# Bats_n_Gons.net
KiCad netlist of a schematic drawn in EAGLE
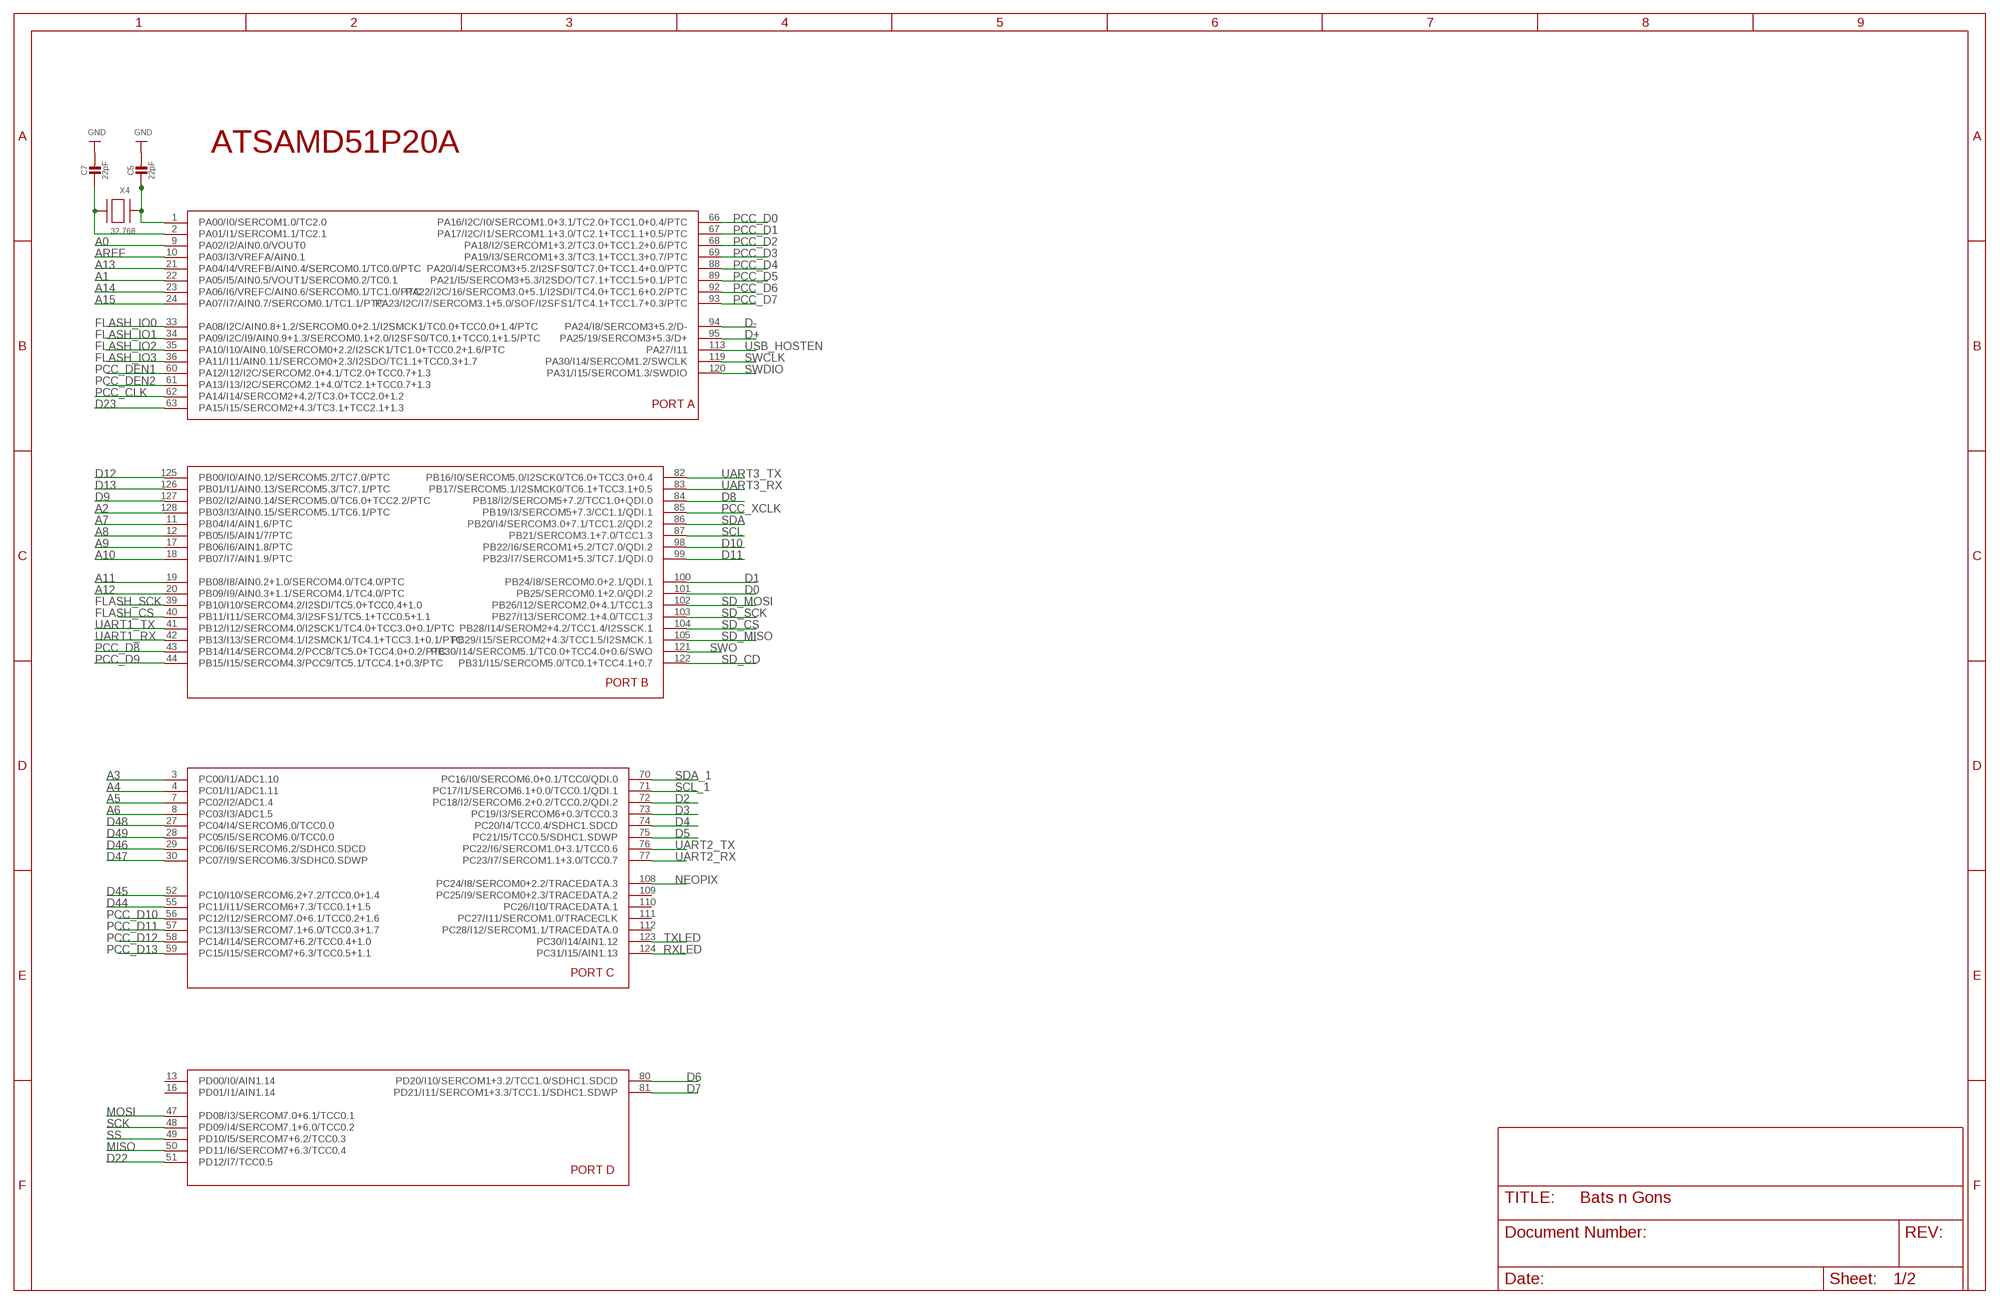
[diagram p0: schematic, sheet 1]
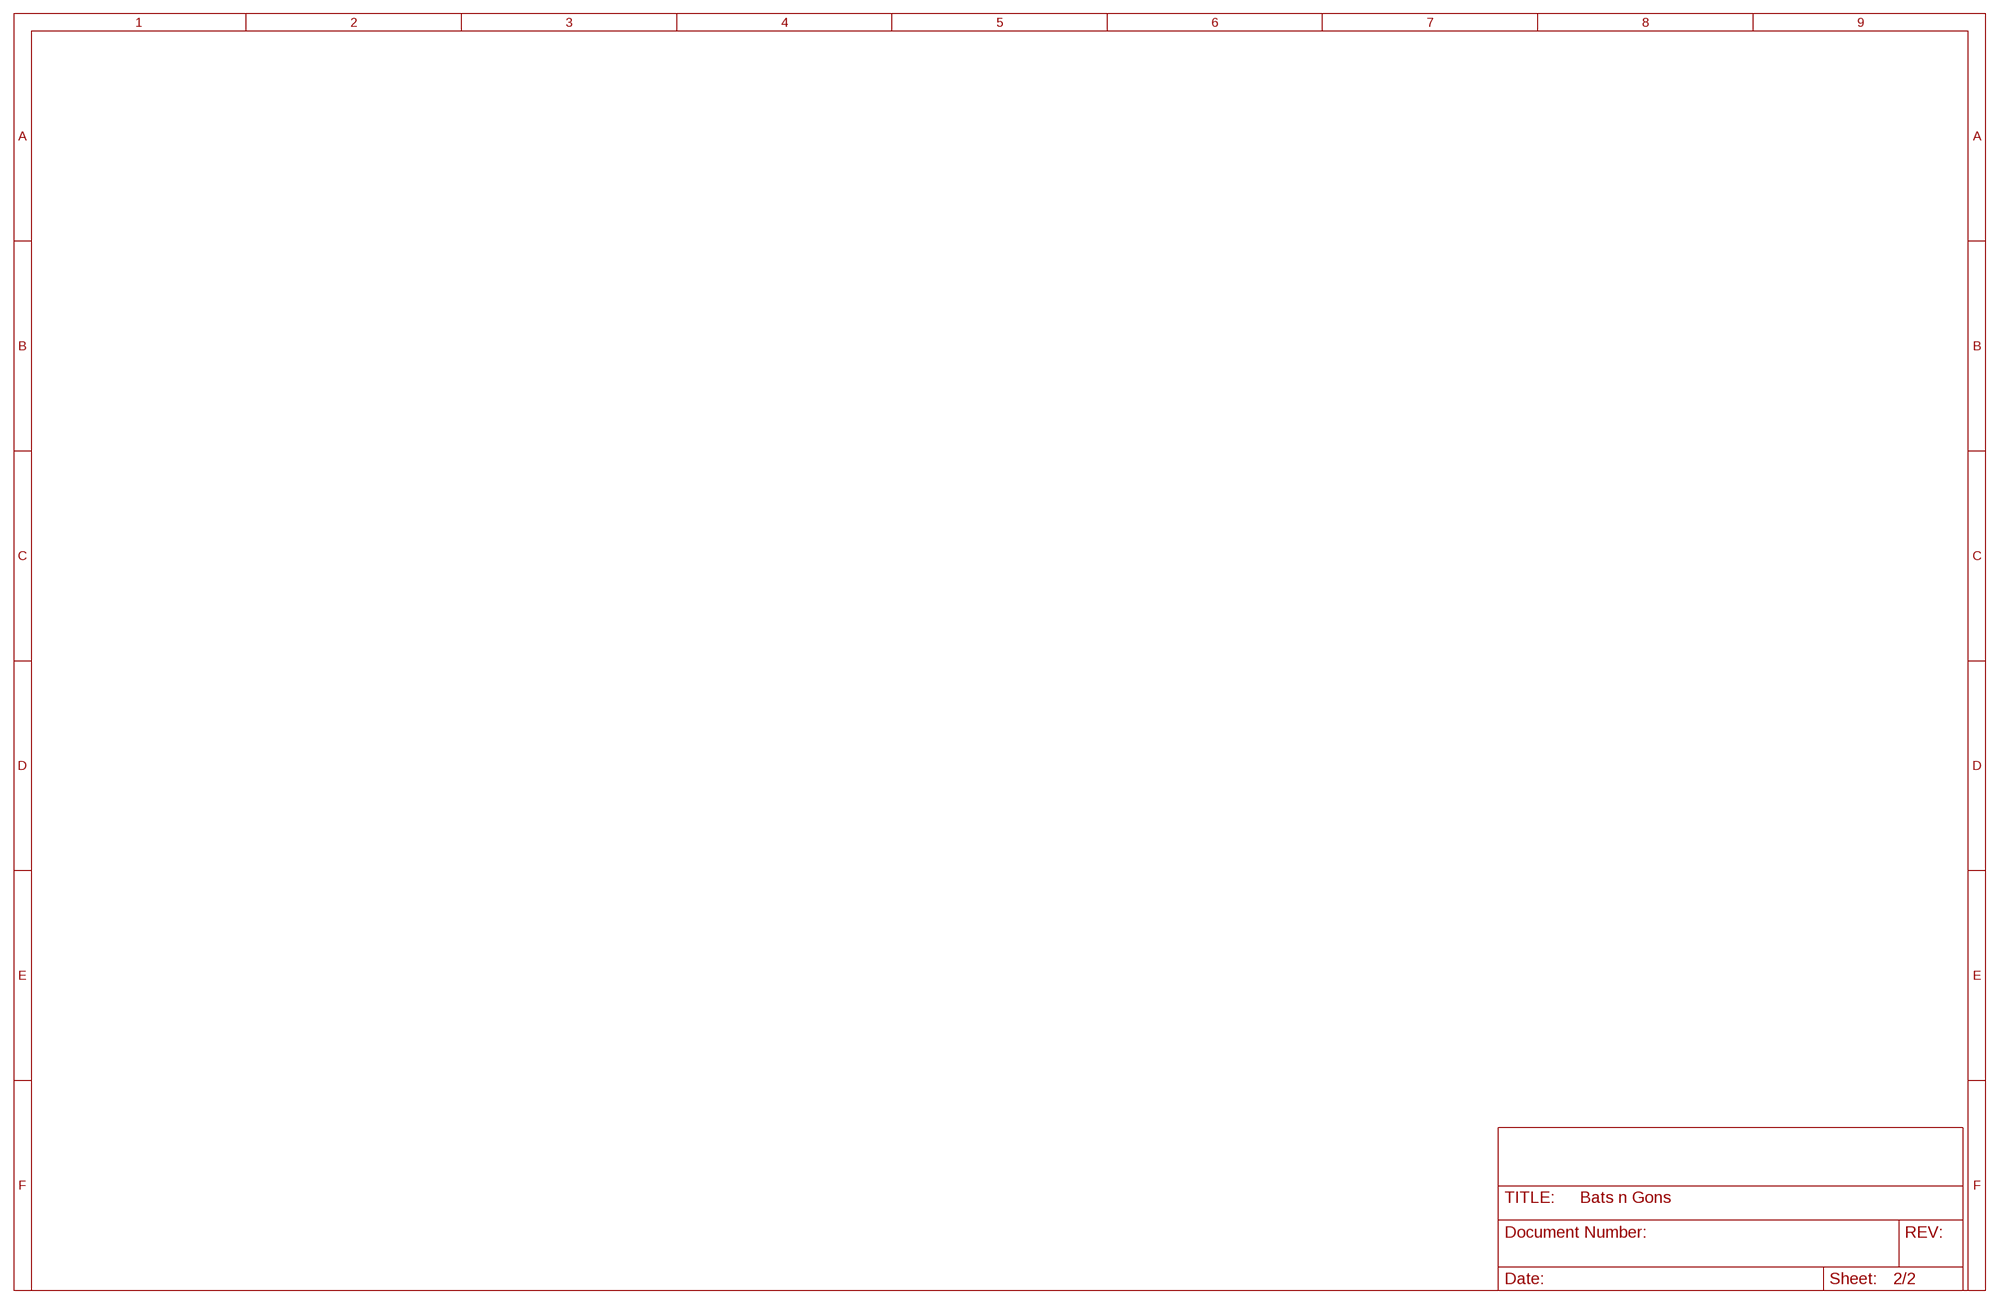
[diagram p1: schematic, sheet 2]

(export (version "E")
  (design (tool "Eeschema 10.0.6"))
  (components
    (comp (ref "C5")
      (value "22pF")
      (footprint "eagle-import:0603-NO")
      (libsource (lib "eagle-import") (part "CAP_CERAMIC0603_NO"))
    )
    (comp (ref "C7")
      (value "22pF")
      (footprint "eagle-import:0603-NO")
      (libsource (lib "eagle-import") (part "CAP_CERAMIC0603_NO"))
    )
    (comp (ref "U$1")
      (value "SAMD51PXXA")
      (footprint "eagle-import:SQFP-S-14X14-128")
      (libsource (lib "eagle-import") (part "SAMD51PXXA"))
    )
    (comp (ref "X4")
      (value "32.768")
      (footprint "eagle-import:XTAL3215")
      (libsource (lib "eagle-import") (part "XTAL-3.2X1.5"))
    )
  )
  (nets
    (net (code "1") (name "A0") (class "Default")
      (node (ref "U$1") (pin "9") (pinfunction "PA02/I2/AIN0.0/VOUT0_9") (pintype "bidirectional"))
    )
    (net (code "2") (name "A1") (class "Default")
      (node (ref "U$1") (pin "22") (pinfunction "PA05/I5/AIN0.5/VOUT1/SERCOM0.2/TC0.1_22") (pintype "bidirectional"))
    )
    (net (code "3") (name "A2") (class "Default")
      (node (ref "U$1") (pin "128") (pinfunction "PB03/I3/AIN0.15/SERCOM5.1/TC6.1/PTC_128") (pintype "bidirectional"))
    )
    (net (code "4") (name "A3") (class "Default")
      (node (ref "U$1") (pin "3") (pinfunction "PC00/I1/ADC1.10_3") (pintype "bidirectional"))
    )
    (net (code "5") (name "A4") (class "Default")
      (node (ref "U$1") (pin "4") (pinfunction "PC01/I1/ADC1.11_4") (pintype "bidirectional"))
    )
    (net (code "6") (name "A5") (class "Default")
      (node (ref "U$1") (pin "7") (pinfunction "PC02/I2/ADC1.4_7") (pintype "bidirectional"))
    )
    (net (code "7") (name "A6") (class "Default")
      (node (ref "U$1") (pin "8") (pinfunction "PC03/I3/ADC1.5_8") (pintype "bidirectional"))
    )
    (net (code "8") (name "A7") (class "Default")
      (node (ref "U$1") (pin "11") (pinfunction "PB04/I4/AIN1.6/PTC_11") (pintype "bidirectional"))
    )
    (net (code "9") (name "A8") (class "Default")
      (node (ref "U$1") (pin "12") (pinfunction "PB05/I5/AIN1/7/PTC_12") (pintype "bidirectional"))
    )
    (net (code "10") (name "A9") (class "Default")
      (node (ref "U$1") (pin "17") (pinfunction "PB06/I6/AIN1.8/PTC_17") (pintype "bidirectional"))
    )
    (net (code "11") (name "A10") (class "Default")
      (node (ref "U$1") (pin "18") (pinfunction "PB07/I7/AIN1.9/PTC_18") (pintype "bidirectional"))
    )
    (net (code "12") (name "A11") (class "Default")
      (node (ref "U$1") (pin "19") (pinfunction "PB08/I8/AIN0.2+1.0/SERCOM4.0/TC4.0/PTC_19") (pintype "bidirectional"))
    )
    (net (code "13") (name "A12") (class "Default")
      (node (ref "U$1") (pin "20") (pinfunction "PB09/I9/AIN0.3+1.1/SERCOM4.1/TC4.0/PTC_20") (pintype "bidirectional"))
    )
    (net (code "14") (name "A13") (class "Default")
      (node (ref "U$1") (pin "21") (pinfunction "PA04/I4/VREFB/AIN0.4/SERCOM0.1/TC0.0/PTC_21") (pintype "bidirectional"))
    )
    (net (code "15") (name "A14") (class "Default")
      (node (ref "U$1") (pin "23") (pinfunction "PA06/I6/VREFC/AIN0.6/SERCOM0.1/TC1.0/PTC_23") (pintype "bidirectional"))
    )
    (net (code "16") (name "A15") (class "Default")
      (node (ref "U$1") (pin "24") (pinfunction "PA07/I7/AIN0.7/SERCOM0.1/TC1.1/PTC_24") (pintype "bidirectional"))
    )
    (net (code "17") (name "AREF") (class "Default")
      (node (ref "U$1") (pin "10") (pinfunction "PA03/I3/VREFA/AIN0.1_10") (pintype "bidirectional"))
    )
    (net (code "18") (name "D+") (class "Default")
      (node (ref "U$1") (pin "95") (pinfunction "PA25/19/SERCOM3+5.3/D+_95") (pintype "bidirectional"))
    )
    (net (code "19") (name "D-") (class "Default")
      (node (ref "U$1") (pin "94") (pinfunction "PA24/I8/SERCOM3+5.2/D-_94") (pintype "bidirectional"))
    )
    (net (code "20") (name "D0") (class "Default")
      (node (ref "U$1") (pin "101") (pinfunction "PB25/SERCOM0.1+2.0/QDI.2_101") (pintype "bidirectional"))
    )
    (net (code "21") (name "D1") (class "Default")
      (node (ref "U$1") (pin "100") (pinfunction "PB24/I8/SERCOM0.0+2.1/QDI.1_100") (pintype "bidirectional"))
    )
    (net (code "22") (name "D2") (class "Default")
      (node (ref "U$1") (pin "72") (pinfunction "PC18/I2/SERCOM6.2+0.2/TCC0.2/QDI.2_72") (pintype "bidirectional"))
    )
    (net (code "23") (name "D3") (class "Default")
      (node (ref "U$1") (pin "73") (pinfunction "PC19/I3/SERCOM6+0.3/TCC0.3_73") (pintype "bidirectional"))
    )
    (net (code "24") (name "D4") (class "Default")
      (node (ref "U$1") (pin "74") (pinfunction "PC20/I4/TCC0.4/SDHC1.SDCD_74") (pintype "bidirectional"))
    )
    (net (code "25") (name "D5") (class "Default")
      (node (ref "U$1") (pin "75") (pinfunction "PC21/I5/TCC0.5/SDHC1.SDWP_75") (pintype "bidirectional"))
    )
    (net (code "26") (name "D6") (class "Default")
      (node (ref "U$1") (pin "80") (pinfunction "PD20/I10/SERCOM1+3.2/TCC1.0/SDHC1.SDCD_80") (pintype "bidirectional"))
    )
    (net (code "27") (name "D7") (class "Default")
      (node (ref "U$1") (pin "81") (pinfunction "PD21/I11/SERCOM1+3.3/TCC1.1/SDHC1.SDWP_81") (pintype "bidirectional"))
    )
    (net (code "28") (name "D8") (class "Default")
      (node (ref "U$1") (pin "84") (pinfunction "PB18/I2/SERCOM5+7.2/TCC1.0+QDI.0_84") (pintype "bidirectional"))
    )
    (net (code "29") (name "D9") (class "Default")
      (node (ref "U$1") (pin "127") (pinfunction "PB02/I2/AIN0.14/SERCOM5.0/TC6.0+TCC2.2/PTC_127") (pintype "bidirectional"))
    )
    (net (code "30") (name "D10") (class "Default")
      (node (ref "U$1") (pin "98") (pinfunction "PB22/I6/SERCOM1+5.2/TC7.0/QDI.2_98") (pintype "bidirectional"))
    )
    (net (code "31") (name "D11") (class "Default")
      (node (ref "U$1") (pin "99") (pinfunction "PB23/I7/SERCOM1+5.3/TC7.1/QDI.0_99") (pintype "bidirectional"))
    )
    (net (code "32") (name "D12") (class "Default")
      (node (ref "U$1") (pin "125") (pinfunction "PB00/I0/AIN0.12/SERCOM5.2/TC7.0/PTC_125") (pintype "bidirectional"))
    )
    (net (code "33") (name "D13") (class "Default")
      (node (ref "U$1") (pin "126") (pinfunction "PB01/I1/AIN0.13/SERCOM5.3/TC7.1/PTC_126") (pintype "bidirectional"))
    )
    (net (code "34") (name "D22") (class "Default")
      (node (ref "U$1") (pin "51") (pinfunction "PD12/I7/TCC0.5_51") (pintype "bidirectional"))
    )
    (net (code "35") (name "D23") (class "Default")
      (node (ref "U$1") (pin "63") (pinfunction "PA15/I15/SERCOM2+4.3/TC3.1+TCC2.1+1.3_63") (pintype "bidirectional"))
    )
    (net (code "36") (name "D44") (class "Default")
      (node (ref "U$1") (pin "55") (pinfunction "PC11/I11/SERCOM6+7.3/TCC0.1+1.5_55") (pintype "bidirectional"))
    )
    (net (code "37") (name "D45") (class "Default")
      (node (ref "U$1") (pin "52") (pinfunction "PC10/I10/SERCOM6.2+7.2/TCC0.0+1.4_52") (pintype "bidirectional"))
    )
    (net (code "38") (name "D46") (class "Default")
      (node (ref "U$1") (pin "29") (pinfunction "PC06/I6/SERCOM6.2/SDHC0.SDCD_29") (pintype "bidirectional"))
    )
    (net (code "39") (name "D47") (class "Default")
      (node (ref "U$1") (pin "30") (pinfunction "PC07/I9/SERCOM6.3/SDHC0.SDWP_30") (pintype "bidirectional"))
    )
    (net (code "40") (name "D48") (class "Default")
      (node (ref "U$1") (pin "27") (pinfunction "PC04/I4/SERCOM6.0/TCC0.0_27") (pintype "bidirectional"))
    )
    (net (code "41") (name "D49") (class "Default")
      (node (ref "U$1") (pin "28") (pinfunction "PC05/I5/SERCOM6.0/TCC0.0_28") (pintype "bidirectional"))
    )
    (net (code "42") (name "FLASH_CS") (class "Default")
      (node (ref "U$1") (pin "40") (pinfunction "PB11/I11/SERCOM4.3/I2SFS1/TC5.1+TCC0.5+1.1_40") (pintype "bidirectional"))
    )
    (net (code "43") (name "FLASH_IO0") (class "Default")
      (node (ref "U$1") (pin "33") (pinfunction "PA08/I2C/AIN0.8+1.2/SERCOM0.0+2.1/I2SMCK1/TC0.0+TCC0.0+1.4/PTC_33") (pintype "bidirectional"))
    )
    (net (code "44") (name "FLASH_IO1") (class "Default")
      (node (ref "U$1") (pin "34") (pinfunction "PA09/I2C/I9/AIN0.9+1.3/SERCOM0.1+2.0/I2SFS0/TC0.1+TCC0.1+1.5/PTC_34") (pintype "bidirectional"))
    )
    (net (code "45") (name "FLASH_IO2") (class "Default")
      (node (ref "U$1") (pin "35") (pinfunction "PA10/I10/AIN0.10/SERCOM0+2.2/I2SCK1/TC1.0+TCC0.2+1.6/PTC_35") (pintype "bidirectional"))
    )
    (net (code "46") (name "FLASH_IO3") (class "Default")
      (node (ref "U$1") (pin "36") (pinfunction "PA11/I11/AIN0.11/SERCOM0+2.3/I2SDO/TC1.1+TCC0.3+1.7_36") (pintype "bidirectional"))
    )
    (net (code "47") (name "FLASH_SCK") (class "Default")
      (node (ref "U$1") (pin "39") (pinfunction "PB10/I10/SERCOM4.2/I2SDI/TC5.0+TCC0.4+1.0_39") (pintype "bidirectional"))
    )
    (net (code "48") (name "GND") (class "Default")
      (node (ref "C5") (pin "2") (pinfunction "2_2") (pintype "passive"))
      (node (ref "C7") (pin "2") (pinfunction "2_2") (pintype "passive"))
    )
    (net (code "49") (name "MISO") (class "Default")
      (node (ref "U$1") (pin "50") (pinfunction "PD11/I6/SERCOM7+6.3/TCC0.4_50") (pintype "bidirectional"))
    )
    (net (code "50") (name "MOSI") (class "Default")
      (node (ref "U$1") (pin "47") (pinfunction "PD08/I3/SERCOM7.0+6.1/TCC0.1_47") (pintype "bidirectional"))
    )
    (net (code "51") (name "NEOPIX") (class "Default")
      (node (ref "U$1") (pin "108") (pinfunction "PC24/I8/SERCOM0+2.2/TRACEDATA.3_108") (pintype "bidirectional"))
    )
    (net (code "52") (name "Net-(U$1A-PA00{slash}I0{slash}SERCOM1.0{slash}TC2.0)") (class "Default")
      (node (ref "C5") (pin "1") (pinfunction "1_1") (pintype "passive"))
      (node (ref "U$1") (pin "1") (pinfunction "PA00/I0/SERCOM1.0/TC2.0_1") (pintype "bidirectional"))
      (node (ref "X4") (pin "P$1") (pinfunction "P$1_P$1") (pintype "bidirectional"))
    )
    (net (code "53") (name "Net-(U$1A-PA01{slash}I1{slash}SERCOM1.1{slash}TC2.1)") (class "Default")
      (node (ref "C7") (pin "1") (pinfunction "1_1") (pintype "passive"))
      (node (ref "U$1") (pin "2") (pinfunction "PA01/I1/SERCOM1.1/TC2.1_2") (pintype "bidirectional"))
      (node (ref "X4") (pin "P$2") (pinfunction "P$2_P$2") (pintype "bidirectional"))
    )
    (net (code "54") (name "PCC_CLK") (class "Default")
      (node (ref "U$1") (pin "62") (pinfunction "PA14/I14/SERCOM2+4.2/TC3.0+TCC2.0+1.2_62") (pintype "bidirectional"))
    )
    (net (code "55") (name "PCC_D0") (class "Default")
      (node (ref "U$1") (pin "66") (pinfunction "PA16/I2C/I0/SERCOM1.0+3.1/TC2.0+TCC1.0+0.4/PTC_66") (pintype "bidirectional"))
    )
    (net (code "56") (name "PCC_D1") (class "Default")
      (node (ref "U$1") (pin "67") (pinfunction "PA17/I2C/I1/SERCOM1.1+3.0/TC2.1+TCC1.1+0.5/PTC_67") (pintype "bidirectional"))
    )
    (net (code "57") (name "PCC_D2") (class "Default")
      (node (ref "U$1") (pin "68") (pinfunction "PA18/I2/SERCOM1+3.2/TC3.0+TCC1.2+0.6/PTC_68") (pintype "bidirectional"))
    )
    (net (code "58") (name "PCC_D3") (class "Default")
      (node (ref "U$1") (pin "69") (pinfunction "PA19/I3/SERCOM1+3.3/TC3.1+TCC1.3+0.7/PTC_69") (pintype "bidirectional"))
    )
    (net (code "59") (name "PCC_D4") (class "Default")
      (node (ref "U$1") (pin "88") (pinfunction "PA20/I4/SERCOM3+5.2/I2SFS0/TC7.0+TCC1.4+0.0/PTC_88") (pintype "bidirectional"))
    )
    (net (code "60") (name "PCC_D5") (class "Default")
      (node (ref "U$1") (pin "89") (pinfunction "PA21/I5/SERCOM3+5.3/I2SDO/TC7.1+TCC1.5+0.1/PTC_89") (pintype "bidirectional"))
    )
    (net (code "61") (name "PCC_D6") (class "Default")
      (node (ref "U$1") (pin "92") (pinfunction "PA22/I2C/16/SERCOM3.0+5.1/I2SDI/TC4.0+TCC1.6+0.2/PTC_92") (pintype "bidirectional"))
    )
    (net (code "62") (name "PCC_D7") (class "Default")
      (node (ref "U$1") (pin "93") (pinfunction "PA23/I2C/I7/SERCOM3.1+5.0/SOF/I2SFS1/TC4.1+TCC1.7+0.3/PTC_93") (pintype "bidirectional"))
    )
    (net (code "63") (name "PCC_D8") (class "Default")
      (node (ref "U$1") (pin "43") (pinfunction "PB14/I14/SERCOM4.2/PCC8/TC5.0+TCC4.0+0.2/PTC_43") (pintype "bidirectional"))
    )
    (net (code "64") (name "PCC_D9") (class "Default")
      (node (ref "U$1") (pin "44") (pinfunction "PB15/I15/SERCOM4.3/PCC9/TC5.1/TCC4.1+0.3/PTC_44") (pintype "bidirectional"))
    )
    (net (code "65") (name "PCC_D10") (class "Default")
      (node (ref "U$1") (pin "56") (pinfunction "PC12/I12/SERCOM7.0+6.1/TCC0.2+1.6_56") (pintype "bidirectional"))
    )
    (net (code "66") (name "PCC_D11") (class "Default")
      (node (ref "U$1") (pin "57") (pinfunction "PC13/I13/SERCOM7.1+6.0/TCC0.3+1.7_57") (pintype "bidirectional"))
    )
    (net (code "67") (name "PCC_D12") (class "Default")
      (node (ref "U$1") (pin "58") (pinfunction "PC14/I14/SERCOM7+6.2/TCC0.4+1.0_58") (pintype "bidirectional"))
    )
    (net (code "68") (name "PCC_D13") (class "Default")
      (node (ref "U$1") (pin "59") (pinfunction "PC15/I15/SERCOM7+6.3/TCC0.5+1.1_59") (pintype "bidirectional"))
    )
    (net (code "69") (name "PCC_DEN1") (class "Default")
      (node (ref "U$1") (pin "60") (pinfunction "PA12/I12/I2C/SERCOM2.0+4.1/TC2.0+TCC0.7+1.3_60") (pintype "bidirectional"))
    )
    (net (code "70") (name "PCC_DEN2") (class "Default")
      (node (ref "U$1") (pin "61") (pinfunction "PA13/I13/I2C/SERCOM2.1+4.0/TC2.1+TCC0.7+1.3_61") (pintype "bidirectional"))
    )
    (net (code "71") (name "PCC_XCLK") (class "Default")
      (node (ref "U$1") (pin "85") (pinfunction "PB19/I3/SERCOM5+7.3/CC1.1/QDI.1_85") (pintype "bidirectional"))
    )
    (net (code "72") (name "RXLED") (class "Default")
      (node (ref "U$1") (pin "124") (pinfunction "PC31/I15/AIN1.13_124") (pintype "bidirectional"))
    )
    (net (code "73") (name "SCK") (class "Default")
      (node (ref "U$1") (pin "48") (pinfunction "PD09/I4/SERCOM7.1+6.0/TCC0.2_48") (pintype "bidirectional"))
    )
    (net (code "74") (name "SCL") (class "Default")
      (node (ref "U$1") (pin "87") (pinfunction "PB21/SERCOM3.1+7.0/TCC1.3_87") (pintype "bidirectional"))
    )
    (net (code "75") (name "SCL_1") (class "Default")
      (node (ref "U$1") (pin "71") (pinfunction "PC17/I1/SERCOM6.1+0.0/TCC0.1/QDI.1_71") (pintype "bidirectional"))
    )
    (net (code "76") (name "SDA") (class "Default")
      (node (ref "U$1") (pin "86") (pinfunction "PB20/I4/SERCOM3.0+7.1/TCC1.2/QDI.2_86") (pintype "bidirectional"))
    )
    (net (code "77") (name "SDA_1") (class "Default")
      (node (ref "U$1") (pin "70") (pinfunction "PC16/I0/SERCOM6.0+0.1/TCC0/QDI.0_70") (pintype "bidirectional"))
    )
    (net (code "78") (name "SD_CD") (class "Default")
      (node (ref "U$1") (pin "122") (pinfunction "PB31/I15/SERCOM5.0/TC0.1+TCC4.1+0.7_122") (pintype "bidirectional"))
    )
    (net (code "79") (name "SD_CS") (class "Default")
      (node (ref "U$1") (pin "104") (pinfunction "PB28/I14/SEROM2+4.2/TCC1.4/I2SSCK.1_104") (pintype "bidirectional"))
    )
    (net (code "80") (name "SD_MISO") (class "Default")
      (node (ref "U$1") (pin "105") (pinfunction "PB29/I15/SERCOM2+4.3/TCC1.5/I2SMCK.1_105") (pintype "bidirectional"))
    )
    (net (code "81") (name "SD_MOSI") (class "Default")
      (node (ref "U$1") (pin "102") (pinfunction "PB26/I12/SERCOM2.0+4.1/TCC1.3_102") (pintype "bidirectional"))
    )
    (net (code "82") (name "SD_SCK") (class "Default")
      (node (ref "U$1") (pin "103") (pinfunction "PB27/I13/SERCOM2.1+4.0/TCC1.3_103") (pintype "bidirectional"))
    )
    (net (code "83") (name "SS") (class "Default")
      (node (ref "U$1") (pin "49") (pinfunction "PD10/I5/SERCOM7+6.2/TCC0.3_49") (pintype "bidirectional"))
    )
    (net (code "84") (name "SWCLK") (class "Default")
      (node (ref "U$1") (pin "119") (pinfunction "PA30/I14/SERCOM1.2/SWCLK_119") (pintype "bidirectional"))
    )
    (net (code "85") (name "SWDIO") (class "Default")
      (node (ref "U$1") (pin "120") (pinfunction "PA31/I15/SERCOM1.3/SWDIO_120") (pintype "bidirectional"))
    )
    (net (code "86") (name "SWO") (class "Default")
      (node (ref "U$1") (pin "121") (pinfunction "PB30/I14/SERCOM5.1/TC0.0+TCC4.0+0.6/SWO_121") (pintype "bidirectional"))
    )
    (net (code "87") (name "TXLED") (class "Default")
      (node (ref "U$1") (pin "123") (pinfunction "PC30/I14/AIN1.12_123") (pintype "bidirectional"))
    )
    (net (code "88") (name "UART1_RX") (class "Default")
      (node (ref "U$1") (pin "42") (pinfunction "PB13/I13/SERCOM4.1/I2SMCK1/TC4.1+TCC3.1+0.1/PTC_42") (pintype "bidirectional"))
    )
    (net (code "89") (name "UART1_TX") (class "Default")
      (node (ref "U$1") (pin "41") (pinfunction "PB12/I12/SERCOM4.0/I2SCK1/TC4.0+TCC3.0+0.1/PTC_41") (pintype "bidirectional"))
    )
    (net (code "90") (name "UART2_RX") (class "Default")
      (node (ref "U$1") (pin "77") (pinfunction "PC23/I7/SERCOM1.1+3.0/TCC0.7_77") (pintype "bidirectional"))
    )
    (net (code "91") (name "UART2_TX") (class "Default")
      (node (ref "U$1") (pin "76") (pinfunction "PC22/I6/SERCOM1.0+3.1/TCC0.6_76") (pintype "bidirectional"))
    )
    (net (code "92") (name "UART3_RX") (class "Default")
      (node (ref "U$1") (pin "83") (pinfunction "PB17/SERCOM5.1/I2SMCK0/TC6.1+TCC3.1+0.5_83") (pintype "bidirectional"))
    )
    (net (code "93") (name "UART3_TX") (class "Default")
      (node (ref "U$1") (pin "82") (pinfunction "PB16/I0/SERCOM5.0/I2SCK0/TC6.0+TCC3.0+0.4_82") (pintype "bidirectional"))
    )
    (net (code "94") (name "USB_HOSTEN") (class "Default")
      (node (ref "U$1") (pin "113") (pinfunction "PA27/I11_113") (pintype "bidirectional"))
    )
    (net (code "95") (name "unconnected-(U$1C-PC25{slash}I9{slash}SERCOM0+2.3{slash}TRACEDATA.2-Pad109)") (class "Default")
      (node (ref "U$1") (pin "109") (pinfunction "PC25/I9/SERCOM0+2.3/TRACEDATA.2_109") (pintype "bidirectional"))
    )
    (net (code "96") (name "unconnected-(U$1C-PC26{slash}I10{slash}TRACEDATA.1-Pad110)") (class "Default")
      (node (ref "U$1") (pin "110") (pinfunction "PC26/I10/TRACEDATA.1_110") (pintype "bidirectional"))
    )
    (net (code "97") (name "unconnected-(U$1C-PC27{slash}I11{slash}SERCOM1.0{slash}TRACECLK-Pad111)") (class "Default")
      (node (ref "U$1") (pin "111") (pinfunction "PC27/I11/SERCOM1.0/TRACECLK_111") (pintype "bidirectional"))
    )
    (net (code "98") (name "unconnected-(U$1C-PC28{slash}I12{slash}SERCOM1.1{slash}TRACEDATA.0-Pad112)") (class "Default")
      (node (ref "U$1") (pin "112") (pinfunction "PC28/I12/SERCOM1.1/TRACEDATA.0_112") (pintype "bidirectional"))
    )
    (net (code "99") (name "unconnected-(U$1D-PD00{slash}I0{slash}AIN1.14-Pad13)") (class "Default")
      (node (ref "U$1") (pin "13") (pinfunction "PD00/I0/AIN1.14_13") (pintype "bidirectional"))
    )
    (net (code "100") (name "unconnected-(U$1D-PD01{slash}I1{slash}AIN1.14-Pad16)") (class "Default")
      (node (ref "U$1") (pin "16") (pinfunction "PD01/I1/AIN1.14_16") (pintype "bidirectional"))
    )
  )
)
